# FLR01A.net
KiCad netlist of a schematic drawn in EAGLE
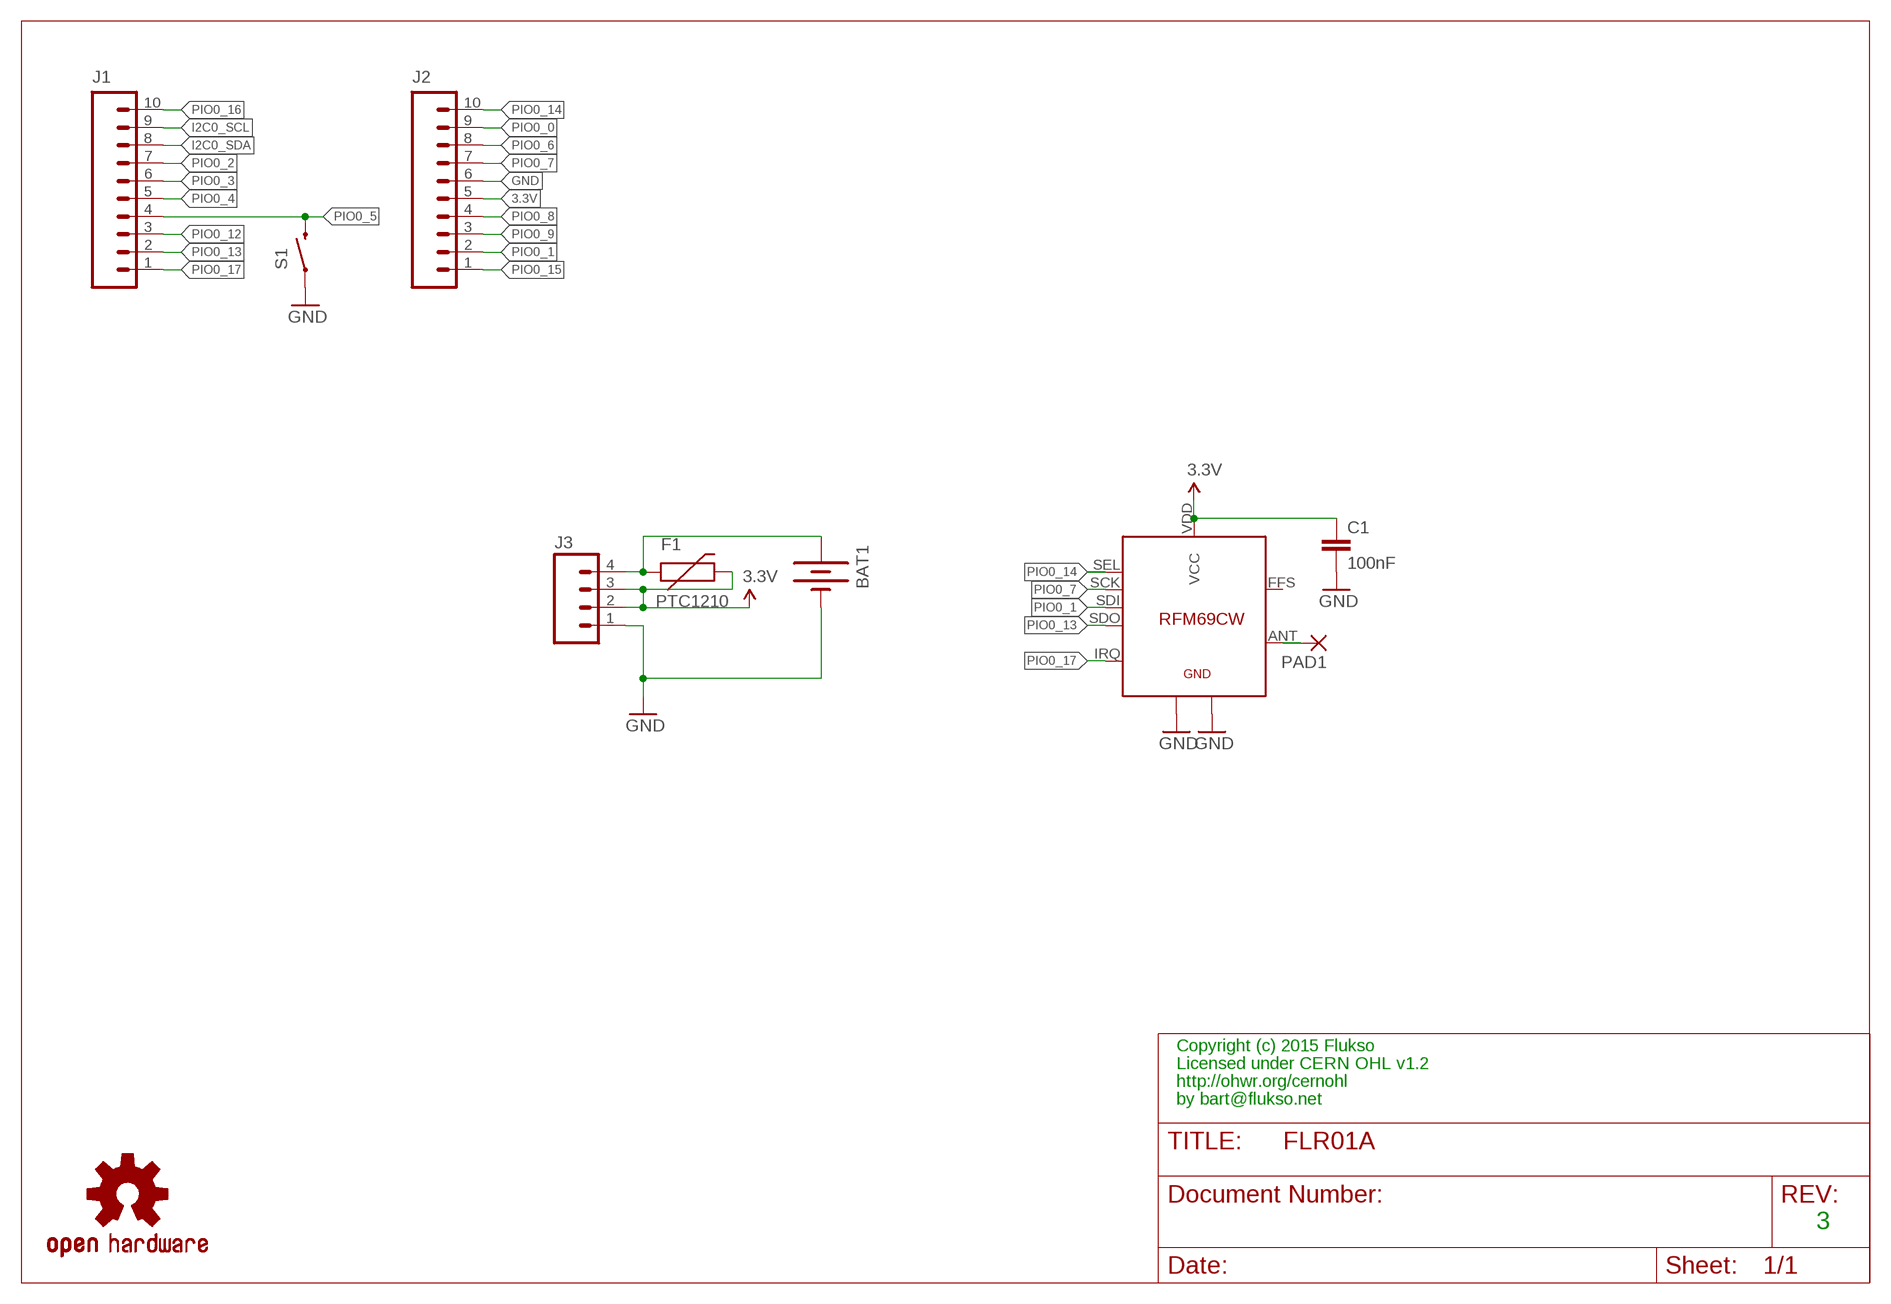
[diagram p0: schematic, sheet 1]

(export (version "E")
  (design (tool "Eeschema 10.0.6"))
  (components
    (comp (ref "BAT1")
      (value "BATTERY245PTH")
      (footprint "eagle-import:BATTCON_245MM_PTH")
      (libsource (lib "eagle-import") (part "BATTERY245PTH"))
    )
    (comp (ref "C1")
      (value "100nF")
      (footprint "eagle-import:0402-CAP")
      (libsource (lib "eagle-import") (part "CAP0402-CAP"))
    )
    (comp (ref "F1")
      (value "PTC1210")
      (footprint "eagle-import:1210")
      (libsource (lib "eagle-import") (part "PTC1210"))
    )
    (comp (ref "J1")
      (value "M10SMD_FEMALE_SHORT")
      (footprint "eagle-import:1X10_SMD_FEMALE_SHORT")
      (libsource (lib "eagle-import") (part "M10SMD_FEMALE_SHORT"))
    )
    (comp (ref "J2")
      (value "M10SMD_FEMALE_SHORT")
      (footprint "eagle-import:1X10_SMD_FEMALE_SHORT")
      (libsource (lib "eagle-import") (part "M10SMD_FEMALE_SHORT"))
    )
    (comp (ref "J3")
      (value "M041X04_NO_SILK")
      (footprint "eagle-import:1X04_NO_SILK")
      (libsource (lib "eagle-import") (part "M041X04_NO_SILK"))
    )
    (comp (ref "PAD1")
      (value "WIREPAD_1,6/0,8")
      (footprint "eagle-import:WIREPAD_1,6_0,8")
      (libsource (lib "eagle-import") (part "WIREPAD_1,6/0,8"))
    )
    (comp (ref "S1")
      (value "SWITCH-MOMENTARY-2SMD")
      (footprint "eagle-import:TACTILE_SWITCH_SMD")
      (libsource (lib "eagle-import") (part "SWITCH-MOMENTARY-2SMD"))
    )
    (comp (ref "U$1")
      (value "OSHW-LOGOS")
      (footprint "eagle-import:OSHW-LOGO-S")
      (libsource (lib "eagle-import") (part "OSHW-LOGOS"))
    )
    (comp (ref "U$2")
      (value "RFM69CW")
      (footprint "eagle-import:RFM69CW")
      (libsource (lib "eagle-import") (part "RFM69CW"))
    )
  )
  (nets
    (net (code "1") (name "3.3V") (class "Default")
      (node (ref "C1") (pin "1") (pinfunction "1_1") (pintype "passive"))
      (node (ref "F1") (pin "2") (pinfunction "2_2") (pintype "bidirectional"))
      (node (ref "J2") (pin "5") (pinfunction "5_5") (pintype "passive"))
      (node (ref "J3") (pin "2") (pinfunction "2_2") (pintype "passive"))
      (node (ref "J3") (pin "3") (pinfunction "3_3") (pintype "passive"))
      (node (ref "U$2") (pin "VDD") (pinfunction "VCC_VDD") (pintype "power_in"))
    )
    (net (code "2") (name "GND") (class "Default")
      (node (ref "BAT1") (pin "2") (pinfunction "-_2") (pintype "power_in"))
      (node (ref "C1") (pin "2") (pinfunction "2_2") (pintype "passive"))
      (node (ref "J2") (pin "6") (pinfunction "6_6") (pintype "passive"))
      (node (ref "J3") (pin "1") (pinfunction "1_1") (pintype "passive"))
      (node (ref "S1") (pin "1") (pinfunction "1_1") (pintype "passive"))
      (node (ref "U$2") (pin "GND1") (pinfunction "GND1_GND1") (pintype "power_in"))
      (node (ref "U$2") (pin "GND2") (pinfunction "GND2_GND2") (pintype "power_in"))
    )
    (net (code "3") (name "I2C0_SCL") (class "Default")
      (node (ref "J1") (pin "9") (pinfunction "9_9") (pintype "passive"))
    )
    (net (code "4") (name "I2C0_SDA") (class "Default")
      (node (ref "J1") (pin "8") (pinfunction "8_8") (pintype "passive"))
    )
    (net (code "5") (name "Net-(BAT1-+)") (class "Default")
      (node (ref "BAT1") (pin "3") (pinfunction "+_3") (pintype "power_in"))
      (node (ref "F1") (pin "1") (pinfunction "1_1") (pintype "bidirectional"))
      (node (ref "J3") (pin "4") (pinfunction "4_4") (pintype "passive"))
    )
    (net (code "6") (name "Net-(PAD1-P)") (class "Default")
      (node (ref "PAD1") (pin "1") (pinfunction "P_1") (pintype "passive"))
      (node (ref "U$2") (pin "ANT") (pinfunction "ANT_ANT") (pintype "passive"))
    )
    (net (code "7") (name "PIO0_0") (class "Default")
      (node (ref "J2") (pin "9") (pinfunction "9_9") (pintype "passive"))
    )
    (net (code "8") (name "PIO0_1") (class "Default")
      (node (ref "J2") (pin "2") (pinfunction "2_2") (pintype "passive"))
      (node (ref "U$2") (pin "SDI") (pinfunction "SDI_SDI") (pintype "input"))
    )
    (net (code "9") (name "PIO0_2") (class "Default")
      (node (ref "J1") (pin "7") (pinfunction "7_7") (pintype "passive"))
    )
    (net (code "10") (name "PIO0_3") (class "Default")
      (node (ref "J1") (pin "6") (pinfunction "6_6") (pintype "passive"))
    )
    (net (code "11") (name "PIO0_4") (class "Default")
      (node (ref "J1") (pin "5") (pinfunction "5_5") (pintype "passive"))
    )
    (net (code "12") (name "PIO0_5") (class "Default")
      (node (ref "J1") (pin "4") (pinfunction "4_4") (pintype "passive"))
      (node (ref "S1") (pin "3") (pinfunction "2_3") (pintype "passive"))
    )
    (net (code "13") (name "PIO0_6") (class "Default")
      (node (ref "J2") (pin "8") (pinfunction "8_8") (pintype "passive"))
    )
    (net (code "14") (name "PIO0_7") (class "Default")
      (node (ref "J2") (pin "7") (pinfunction "7_7") (pintype "passive"))
      (node (ref "U$2") (pin "SCK") (pinfunction "SCK_SCK") (pintype "input"))
    )
    (net (code "15") (name "PIO0_8") (class "Default")
      (node (ref "J2") (pin "4") (pinfunction "4_4") (pintype "passive"))
    )
    (net (code "16") (name "PIO0_9") (class "Default")
      (node (ref "J2") (pin "3") (pinfunction "3_3") (pintype "passive"))
    )
    (net (code "17") (name "PIO0_12") (class "Default")
      (node (ref "J1") (pin "3") (pinfunction "3_3") (pintype "passive"))
    )
    (net (code "18") (name "PIO0_13") (class "Default")
      (node (ref "J1") (pin "2") (pinfunction "2_2") (pintype "passive"))
      (node (ref "U$2") (pin "SDO") (pinfunction "SDO_SDO") (pintype "output"))
    )
    (net (code "19") (name "PIO0_14") (class "Default")
      (node (ref "J2") (pin "10") (pinfunction "10_10") (pintype "passive"))
      (node (ref "U$2") (pin "SEL") (pinfunction "SEL_SEL") (pintype "input"))
    )
    (net (code "20") (name "PIO0_15") (class "Default")
      (node (ref "J2") (pin "1") (pinfunction "1_1") (pintype "passive"))
    )
    (net (code "21") (name "PIO0_16") (class "Default")
      (node (ref "J1") (pin "10") (pinfunction "10_10") (pintype "passive"))
    )
    (net (code "22") (name "PIO0_17") (class "Default")
      (node (ref "J1") (pin "1") (pinfunction "1_1") (pintype "passive"))
      (node (ref "U$2") (pin "IRQ") (pinfunction "IRQ_IRQ") (pintype "open_collector"))
    )
    (net (code "23") (name "unconnected-(U$2-PadFFS)") (class "Default")
      (node (ref "U$2") (pin "FFS") (pinfunction "FFS_FFS") (pintype "bidirectional"))
    )
  )
)
